# LCD.net
KiCad netlist of a schematic drawn in Altium Designer
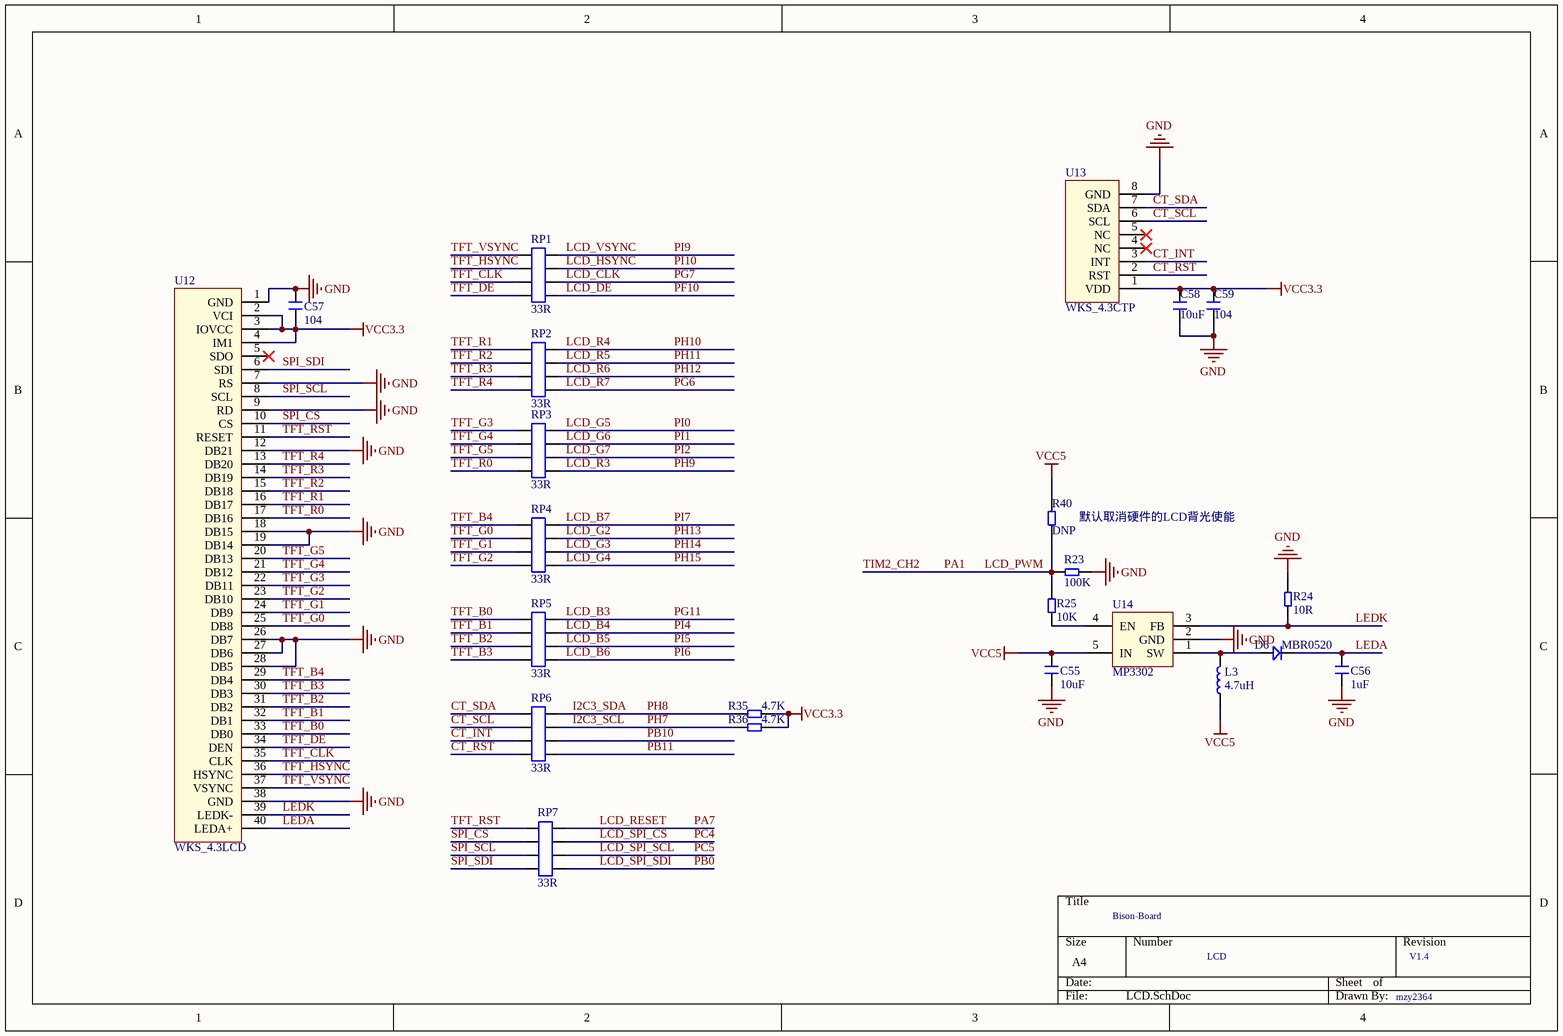
[diagram p0: LCD.SchDoc]

(export (version "E")
  (design (tool "Eeschema 10.0.6"))
  (components
    (comp (ref "C55") (value "10uF") (footprint "C 0805") (libsource (lib "Bison-Board") (part "CAP")))
    (comp (ref "C56") (value "1uF") (footprint "C 0603") (libsource (lib "Bison-Board") (part "CAP")))
    (comp (ref "C57") (value "104") (footprint "C 0603") (libsource (lib "Bison-Board") (part "CAP")))
    (comp (ref "C58") (value "10uF") (footprint "C 0805") (libsource (lib "Bison-Board") (part "CAP")))
    (comp (ref "C59") (value "104") (footprint "C 0603") (libsource (lib "Bison-Board") (part "CAP")))
    (comp (ref "D6") (value "MBR0520") (footprint "SOD123") (libsource (lib "Bison-Board") (part "Diode")))
    (comp (ref "L3") (value "4.7uH") (footprint "L_SMNR4030") (libsource (lib "squ-guiboard") (part "L")))
    (comp (ref "R23") (value "100K") (footprint "R 0603") (libsource (lib "Bison-Board") (part "RES")))
    (comp (ref "R24") (value "10R") (footprint "R 0603") (libsource (lib "Bison-Board") (part "RES")))
    (comp (ref "R25") (value "10K") (footprint "R 0603") (libsource (lib "Bison-Board") (part "RES")))
    (comp (ref "R35") (value "4.7K") (footprint "R 0603") (libsource (lib "Bison-Board") (part "RES")))
    (comp (ref "R36") (value "4.7K") (footprint "R 0603") (libsource (lib "Bison-Board") (part "RES")))
    (comp (ref "R40") (value "DNP") (footprint "R 0603") (libsource (lib "Bison-Board") (part "RES")))
    (comp (ref "RP1") (value "33R") (footprint "8P4R 0603") (libsource (lib "Bison-Board") (part "RP")))
    (comp (ref "RP2") (value "33R") (footprint "8P4R 0603") (libsource (lib "Bison-Board") (part "RP")))
    (comp (ref "RP3") (value "33R") (footprint "8P4R 0603") (libsource (lib "Bison-Board") (part "RP")))
    (comp (ref "RP4") (value "33R") (footprint "8P4R 0603") (libsource (lib "Bison-Board") (part "RP")))
    (comp (ref "RP5") (value "33R") (footprint "8P4R 0603") (libsource (lib "Bison-Board") (part "RP")))
    (comp (ref "RP6") (value "33R") (footprint "8P4R 0603") (libsource (lib "Bison-Board") (part "RP")))
    (comp (ref "RP7") (value "33R") (footprint "8P4R 0603") (libsource (lib "Bison-Board") (part "RP")))
    (comp (ref "U12")
      (value "WKS_4.3LCD")
      (footprint "FPC0.5-40P")
      (libsource (lib "Bison-Board") (part "WKS_4.3LCD"))
    )
    (comp (ref "U13")
      (value "WKS_4.3CTP")
      (footprint "FPC0.5-8P")
      (libsource (lib "Bison-Board") (part "WKS_4.3CTP"))
    )
    (comp (ref "U14")
      (value "MP3302")
      (footprint "SOT23-5")
      (description "LED驱动IC")
      (libsource (lib "Bison-Board") (part "MP3302"))
    )
  )
  (nets
    (net (code "1") (name "/CT_INT") (class "Default")
      (node (ref "RP6") (pin "3") (pinfunction "3_3") (pintype "passive"))
      (node (ref "U13") (pin "3") (pinfunction "INT_3") (pintype "passive"))
    )
    (net (code "2") (name "/CT_RST") (class "Default")
      (node (ref "RP6") (pin "4") (pinfunction "4_4") (pintype "passive"))
      (node (ref "U13") (pin "2") (pinfunction "RST_2") (pintype "passive"))
    )
    (net (code "3") (name "/CT_SCL") (class "Default")
      (node (ref "RP6") (pin "2") (pinfunction "2_2") (pintype "passive"))
      (node (ref "U13") (pin "6") (pinfunction "SCL_6") (pintype "passive"))
    )
    (net (code "4") (name "/CT_SDA") (class "Default")
      (node (ref "RP6") (pin "1") (pinfunction "1_1") (pintype "passive"))
      (node (ref "U13") (pin "7") (pinfunction "SDA_7") (pintype "passive"))
    )
    (net (code "5") (name "/I2C3_SCL") (class "Default")
      (node (ref "R36") (pin "1") (pintype "passive"))
      (node (ref "RP6") (pin "7") (pinfunction "7_7") (pintype "passive"))
    )
    (net (code "6") (name "/I2C3_SDA") (class "Default")
      (node (ref "R35") (pin "1") (pintype "passive"))
      (node (ref "RP6") (pin "8") (pinfunction "8_8") (pintype "passive"))
    )
    (net (code "7") (name "/LCD_B3") (class "Default")
      (node (ref "RP5") (pin "8") (pinfunction "8_8") (pintype "passive"))
    )
    (net (code "8") (name "/LCD_B4") (class "Default")
      (node (ref "RP5") (pin "7") (pinfunction "7_7") (pintype "passive"))
    )
    (net (code "9") (name "/LCD_B5") (class "Default")
      (node (ref "RP5") (pin "6") (pinfunction "6_6") (pintype "passive"))
    )
    (net (code "10") (name "/LCD_B6") (class "Default")
      (node (ref "RP5") (pin "5") (pinfunction "5_5") (pintype "passive"))
    )
    (net (code "11") (name "/LCD_B7") (class "Default")
      (node (ref "RP4") (pin "8") (pinfunction "8_8") (pintype "passive"))
    )
    (net (code "12") (name "/LCD_CLK") (class "Default")
      (node (ref "RP1") (pin "6") (pinfunction "6_6") (pintype "passive"))
    )
    (net (code "13") (name "/LCD_DE") (class "Default")
      (node (ref "RP1") (pin "5") (pinfunction "5_5") (pintype "passive"))
    )
    (net (code "14") (name "/LCD_G2") (class "Default")
      (node (ref "RP4") (pin "7") (pinfunction "7_7") (pintype "passive"))
    )
    (net (code "15") (name "/LCD_G3") (class "Default")
      (node (ref "RP4") (pin "6") (pinfunction "6_6") (pintype "passive"))
    )
    (net (code "16") (name "/LCD_G4") (class "Default")
      (node (ref "RP4") (pin "5") (pinfunction "5_5") (pintype "passive"))
    )
    (net (code "17") (name "/LCD_G5") (class "Default")
      (node (ref "RP3") (pin "8") (pinfunction "8_8") (pintype "passive"))
    )
    (net (code "18") (name "/LCD_G6") (class "Default")
      (node (ref "RP3") (pin "7") (pinfunction "7_7") (pintype "passive"))
    )
    (net (code "19") (name "/LCD_G7") (class "Default")
      (node (ref "RP3") (pin "6") (pinfunction "6_6") (pintype "passive"))
    )
    (net (code "20") (name "/LCD_HSYNC") (class "Default")
      (node (ref "RP1") (pin "7") (pinfunction "7_7") (pintype "passive"))
    )
    (net (code "21") (name "/LCD_PWM") (class "Default")
      (node (ref "R23") (pin "1") (pintype "passive"))
      (node (ref "R25") (pin "1") (pintype "passive"))
      (node (ref "R40") (pin "1") (pintype "passive"))
    )
    (net (code "22") (name "/LCD_R3") (class "Default")
      (node (ref "RP3") (pin "5") (pinfunction "5_5") (pintype "passive"))
    )
    (net (code "23") (name "/LCD_R4") (class "Default")
      (node (ref "RP2") (pin "8") (pinfunction "8_8") (pintype "passive"))
    )
    (net (code "24") (name "/LCD_R5") (class "Default")
      (node (ref "RP2") (pin "7") (pinfunction "7_7") (pintype "passive"))
    )
    (net (code "25") (name "/LCD_R6") (class "Default")
      (node (ref "RP2") (pin "6") (pinfunction "6_6") (pintype "passive"))
    )
    (net (code "26") (name "/LCD_R7") (class "Default")
      (node (ref "RP2") (pin "5") (pinfunction "5_5") (pintype "passive"))
    )
    (net (code "27") (name "/LCD_RESET") (class "Default")
      (node (ref "RP7") (pin "8") (pinfunction "8_8") (pintype "passive"))
    )
    (net (code "28") (name "/LCD_SPI_CS") (class "Default")
      (node (ref "RP7") (pin "7") (pinfunction "7_7") (pintype "passive"))
    )
    (net (code "29") (name "/LCD_SPI_SCL") (class "Default")
      (node (ref "RP7") (pin "6") (pinfunction "6_6") (pintype "passive"))
    )
    (net (code "30") (name "/LCD_SPI_SDI") (class "Default")
      (node (ref "RP7") (pin "5") (pinfunction "5_5") (pintype "passive"))
    )
    (net (code "31") (name "/LCD_VSYNC") (class "Default")
      (node (ref "RP1") (pin "8") (pinfunction "8_8") (pintype "passive"))
    )
    (net (code "32") (name "/LEDA") (class "Default")
      (node (ref "C56") (pin "2") (pinfunction "2_2") (pintype "passive"))
      (node (ref "D6") (pin "2") (pintype "passive"))
      (node (ref "U12") (pin "40") (pinfunction "LEDA+_40") (pintype "passive"))
    )
    (net (code "33") (name "/LEDK") (class "Default")
      (node (ref "R24") (pin "1") (pintype "passive"))
      (node (ref "U12") (pin "39") (pinfunction "LEDK-_39") (pintype "passive"))
      (node (ref "U14") (pin "3") (pinfunction "FB_3") (pintype "passive"))
    )
    (net (code "34") (name "/PB10") (class "Default")
      (node (ref "RP6") (pin "6") (pinfunction "6_6") (pintype "passive"))
    )
    (net (code "35") (name "/PB11") (class "Default")
      (node (ref "RP6") (pin "5") (pinfunction "5_5") (pintype "passive"))
    )
    (net (code "36") (name "/SPI_CS") (class "Default")
      (node (ref "RP7") (pin "2") (pinfunction "2_2") (pintype "passive"))
      (node (ref "U12") (pin "10") (pinfunction "CS_10") (pintype "passive"))
    )
    (net (code "37") (name "/SPI_SCL") (class "Default")
      (node (ref "RP7") (pin "3") (pinfunction "3_3") (pintype "passive"))
      (node (ref "U12") (pin "8") (pinfunction "SCL_8") (pintype "passive"))
    )
    (net (code "38") (name "/SPI_SDI") (class "Default")
      (node (ref "RP7") (pin "4") (pinfunction "4_4") (pintype "passive"))
      (node (ref "U12") (pin "6") (pinfunction "SDI_6") (pintype "passive"))
    )
    (net (code "39") (name "/TFT_B0") (class "Default")
      (node (ref "RP5") (pin "1") (pinfunction "1_1") (pintype "passive"))
      (node (ref "U12") (pin "33") (pinfunction "DB0_33") (pintype "passive"))
    )
    (net (code "40") (name "/TFT_B1") (class "Default")
      (node (ref "RP5") (pin "2") (pinfunction "2_2") (pintype "passive"))
      (node (ref "U12") (pin "32") (pinfunction "DB1_32") (pintype "passive"))
    )
    (net (code "41") (name "/TFT_B2") (class "Default")
      (node (ref "RP5") (pin "3") (pinfunction "3_3") (pintype "passive"))
      (node (ref "U12") (pin "31") (pinfunction "DB2_31") (pintype "passive"))
    )
    (net (code "42") (name "/TFT_B3") (class "Default")
      (node (ref "RP5") (pin "4") (pinfunction "4_4") (pintype "passive"))
      (node (ref "U12") (pin "30") (pinfunction "DB3_30") (pintype "passive"))
    )
    (net (code "43") (name "/TFT_B4") (class "Default")
      (node (ref "RP4") (pin "1") (pinfunction "1_1") (pintype "passive"))
      (node (ref "U12") (pin "29") (pinfunction "DB4_29") (pintype "passive"))
    )
    (net (code "44") (name "/TFT_CLK") (class "Default")
      (node (ref "RP1") (pin "3") (pinfunction "3_3") (pintype "passive"))
      (node (ref "U12") (pin "35") (pinfunction "CLK_35") (pintype "passive"))
    )
    (net (code "45") (name "/TFT_DE") (class "Default")
      (node (ref "RP1") (pin "4") (pinfunction "4_4") (pintype "passive"))
      (node (ref "U12") (pin "34") (pinfunction "DEN_34") (pintype "passive"))
    )
    (net (code "46") (name "/TFT_G0") (class "Default")
      (node (ref "RP4") (pin "2") (pinfunction "2_2") (pintype "passive"))
      (node (ref "U12") (pin "25") (pinfunction "DB8_25") (pintype "passive"))
    )
    (net (code "47") (name "/TFT_G1") (class "Default")
      (node (ref "RP4") (pin "3") (pinfunction "3_3") (pintype "passive"))
      (node (ref "U12") (pin "24") (pinfunction "DB9_24") (pintype "passive"))
    )
    (net (code "48") (name "/TFT_G2") (class "Default")
      (node (ref "RP4") (pin "4") (pinfunction "4_4") (pintype "passive"))
      (node (ref "U12") (pin "23") (pinfunction "DB10_23") (pintype "passive"))
    )
    (net (code "49") (name "/TFT_G3") (class "Default")
      (node (ref "RP3") (pin "1") (pinfunction "1_1") (pintype "passive"))
      (node (ref "U12") (pin "22") (pinfunction "DB11_22") (pintype "passive"))
    )
    (net (code "50") (name "/TFT_G4") (class "Default")
      (node (ref "RP3") (pin "2") (pinfunction "2_2") (pintype "passive"))
      (node (ref "U12") (pin "21") (pinfunction "DB12_21") (pintype "passive"))
    )
    (net (code "51") (name "/TFT_G5") (class "Default")
      (node (ref "RP3") (pin "3") (pinfunction "3_3") (pintype "passive"))
      (node (ref "U12") (pin "20") (pinfunction "DB13_20") (pintype "passive"))
    )
    (net (code "52") (name "/TFT_HSYNC") (class "Default")
      (node (ref "RP1") (pin "2") (pinfunction "2_2") (pintype "passive"))
      (node (ref "U12") (pin "36") (pinfunction "HSYNC_36") (pintype "passive"))
    )
    (net (code "53") (name "/TFT_R0") (class "Default")
      (node (ref "RP3") (pin "4") (pinfunction "4_4") (pintype "passive"))
      (node (ref "U12") (pin "17") (pinfunction "DB16_17") (pintype "passive"))
    )
    (net (code "54") (name "/TFT_R1") (class "Default")
      (node (ref "RP2") (pin "1") (pinfunction "1_1") (pintype "passive"))
      (node (ref "U12") (pin "16") (pinfunction "DB17_16") (pintype "passive"))
    )
    (net (code "55") (name "/TFT_R2") (class "Default")
      (node (ref "RP2") (pin "2") (pinfunction "2_2") (pintype "passive"))
      (node (ref "U12") (pin "15") (pinfunction "DB18_15") (pintype "passive"))
    )
    (net (code "56") (name "/TFT_R3") (class "Default")
      (node (ref "RP2") (pin "3") (pinfunction "3_3") (pintype "passive"))
      (node (ref "U12") (pin "14") (pinfunction "DB19_14") (pintype "passive"))
    )
    (net (code "57") (name "/TFT_R4") (class "Default")
      (node (ref "RP2") (pin "4") (pinfunction "4_4") (pintype "passive"))
      (node (ref "U12") (pin "13") (pinfunction "DB20_13") (pintype "passive"))
    )
    (net (code "58") (name "/TFT_RST") (class "Default")
      (node (ref "RP7") (pin "1") (pinfunction "1_1") (pintype "passive"))
      (node (ref "U12") (pin "11") (pinfunction "RESET_11") (pintype "passive"))
    )
    (net (code "59") (name "/TFT_VSYNC") (class "Default")
      (node (ref "RP1") (pin "1") (pinfunction "1_1") (pintype "passive"))
      (node (ref "U12") (pin "37") (pinfunction "VSYNC_37") (pintype "passive"))
    )
    (net (code "60") (name "GND") (class "Default")
      (node (ref "C55") (pin "1") (pinfunction "1_1") (pintype "passive"))
      (node (ref "C56") (pin "1") (pinfunction "1_1") (pintype "passive"))
      (node (ref "C57") (pin "2") (pinfunction "2_2") (pintype "passive"))
      (node (ref "C58") (pin "1") (pinfunction "1_1") (pintype "passive"))
      (node (ref "C59") (pin "1") (pinfunction "1_1") (pintype "passive"))
      (node (ref "R23") (pin "2") (pintype "passive"))
      (node (ref "R24") (pin "2") (pintype "passive"))
      (node (ref "U12") (pin "1") (pinfunction "GND_1") (pintype "passive"))
      (node (ref "U12") (pin "12") (pinfunction "DB21_12") (pintype "passive"))
      (node (ref "U12") (pin "18") (pinfunction "DB15_18") (pintype "passive"))
      (node (ref "U12") (pin "19") (pinfunction "DB14_19") (pintype "passive"))
      (node (ref "U12") (pin "26") (pinfunction "DB7_26") (pintype "passive"))
      (node (ref "U12") (pin "27") (pinfunction "DB6_27") (pintype "passive"))
      (node (ref "U12") (pin "28") (pinfunction "DB5_28") (pintype "passive"))
      (node (ref "U12") (pin "38") (pinfunction "GND_38") (pintype "passive"))
      (node (ref "U12") (pin "7") (pinfunction "RS_7") (pintype "passive"))
      (node (ref "U12") (pin "9") (pinfunction "RD_9") (pintype "passive"))
      (node (ref "U13") (pin "8") (pinfunction "GND_8") (pintype "passive"))
      (node (ref "U14") (pin "2") (pinfunction "GND_2") (pintype "passive"))
    )
    (net (code "61") (name "Net-(U14-EN)") (class "Default")
      (node (ref "R25") (pin "2") (pintype "passive"))
      (node (ref "U14") (pin "4") (pinfunction "EN_4") (pintype "passive"))
    )
    (net (code "62") (name "Net-(U14-SW)") (class "Default")
      (node (ref "D6") (pin "1") (pintype "passive"))
      (node (ref "L3") (pin "1") (pinfunction "1_1") (pintype "passive"))
      (node (ref "U14") (pin "1") (pinfunction "SW_1") (pintype "passive"))
    )
    (net (code "63") (name "VCC3.3") (class "Default")
      (node (ref "C57") (pin "1") (pinfunction "1_1") (pintype "passive"))
      (node (ref "C58") (pin "2") (pinfunction "2_2") (pintype "passive"))
      (node (ref "C59") (pin "2") (pinfunction "2_2") (pintype "passive"))
      (node (ref "R35") (pin "2") (pintype "passive"))
      (node (ref "R36") (pin "2") (pintype "passive"))
      (node (ref "U12") (pin "2") (pinfunction "VCI_2") (pintype "passive"))
      (node (ref "U12") (pin "3") (pinfunction "IOVCC_3") (pintype "passive"))
      (node (ref "U12") (pin "4") (pinfunction "IM1_4") (pintype "passive"))
      (node (ref "U13") (pin "1") (pinfunction "VDD_1") (pintype "passive"))
    )
    (net (code "64") (name "VCC5") (class "Default")
      (node (ref "C55") (pin "2") (pinfunction "2_2") (pintype "passive"))
      (node (ref "L3") (pin "2") (pinfunction "2_2") (pintype "passive"))
      (node (ref "R40") (pin "2") (pintype "passive"))
      (node (ref "U14") (pin "5") (pinfunction "IN_5") (pintype "passive"))
    )
    (net (code "65") (name "unconnected-(U12-SDO-Pad5)") (class "Default")
      (node (ref "U12") (pin "5") (pinfunction "SDO_5") (pintype "passive+no_connect"))
    )
    (net (code "66") (name "unconnected-(U13-NC-Pad4)") (class "Default")
      (node (ref "U13") (pin "4") (pinfunction "NC_4") (pintype "passive+no_connect"))
    )
    (net (code "67") (name "unconnected-(U13-NC-Pad5)") (class "Default")
      (node (ref "U13") (pin "5") (pinfunction "NC_5") (pintype "passive+no_connect"))
    )
  )
)
